# LEDMatrix.net
KiCad netlist of a schematic drawn in EAGLE
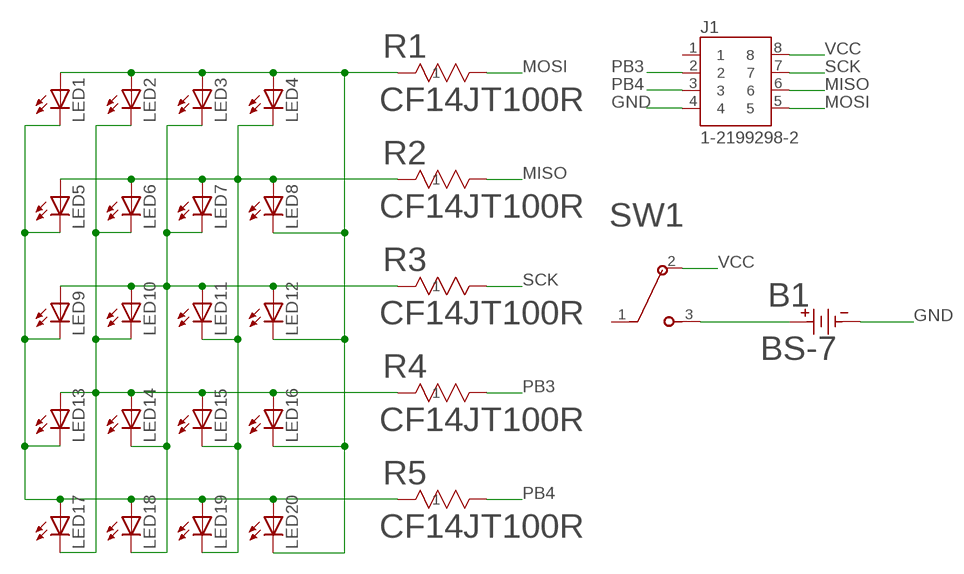
[diagram p0: schematic, sheet 1]

(export (version "E")
  (design (tool "Eeschema 10.0.6"))
  (components
    (comp (ref "B1")
      (value "BS-7")
      (footprint "eagle-import:BS-7_MPD")
      (fields (field (name "COPYRIGHT") "Copyright (C) 2018 Accelerated Designs. All rights reserved"))
      (libsource (lib "eagle-import") (part "BS-7"))
    )
    (comp (ref "J1")
      (value "1-2199298-2")
      (footprint "eagle-import:TE_1-2199298-2")
      (fields (field (name "DIGI-KEY_PART_NUMBER") "A120347-ND") (field (name "MF") "TE Connectivity"))
      (libsource (lib "eagle-import") (part "1-2199298-2"))
    )
    (comp (ref "LED1")
      (value "LED3MM")
      (footprint "eagle-import:LED3MM")
      (libsource (lib "eagle-import") (part "LED3MM"))
    )
    (comp (ref "LED2")
      (value "LED3MM")
      (footprint "eagle-import:LED3MM")
      (libsource (lib "eagle-import") (part "LED3MM"))
    )
    (comp (ref "LED3")
      (value "LED3MM")
      (footprint "eagle-import:LED3MM")
      (libsource (lib "eagle-import") (part "LED3MM"))
    )
    (comp (ref "LED4")
      (value "LED3MM")
      (footprint "eagle-import:LED3MM")
      (libsource (lib "eagle-import") (part "LED3MM"))
    )
    (comp (ref "LED5")
      (value "LED3MM")
      (footprint "eagle-import:LED3MM")
      (libsource (lib "eagle-import") (part "LED3MM"))
    )
    (comp (ref "LED6")
      (value "LED3MM")
      (footprint "eagle-import:LED3MM")
      (libsource (lib "eagle-import") (part "LED3MM"))
    )
    (comp (ref "LED7")
      (value "LED3MM")
      (footprint "eagle-import:LED3MM")
      (libsource (lib "eagle-import") (part "LED3MM"))
    )
    (comp (ref "LED8")
      (value "LED3MM")
      (footprint "eagle-import:LED3MM")
      (libsource (lib "eagle-import") (part "LED3MM"))
    )
    (comp (ref "LED9")
      (value "LED3MM")
      (footprint "eagle-import:LED3MM")
      (libsource (lib "eagle-import") (part "LED3MM"))
    )
    (comp (ref "LED10")
      (value "LED3MM")
      (footprint "eagle-import:LED3MM")
      (libsource (lib "eagle-import") (part "LED3MM"))
    )
    (comp (ref "LED11")
      (value "LED3MM")
      (footprint "eagle-import:LED3MM")
      (libsource (lib "eagle-import") (part "LED3MM"))
    )
    (comp (ref "LED12")
      (value "LED3MM")
      (footprint "eagle-import:LED3MM")
      (libsource (lib "eagle-import") (part "LED3MM"))
    )
    (comp (ref "LED13")
      (value "LED3MM")
      (footprint "eagle-import:LED3MM")
      (libsource (lib "eagle-import") (part "LED3MM"))
    )
    (comp (ref "LED14")
      (value "LED3MM")
      (footprint "eagle-import:LED3MM")
      (libsource (lib "eagle-import") (part "LED3MM"))
    )
    (comp (ref "LED15")
      (value "LED3MM")
      (footprint "eagle-import:LED3MM")
      (libsource (lib "eagle-import") (part "LED3MM"))
    )
    (comp (ref "LED16")
      (value "LED3MM")
      (footprint "eagle-import:LED3MM")
      (libsource (lib "eagle-import") (part "LED3MM"))
    )
    (comp (ref "LED17")
      (value "LED3MM")
      (footprint "eagle-import:LED3MM")
      (libsource (lib "eagle-import") (part "LED3MM"))
    )
    (comp (ref "LED18")
      (value "LED3MM")
      (footprint "eagle-import:LED3MM")
      (libsource (lib "eagle-import") (part "LED3MM"))
    )
    (comp (ref "LED19")
      (value "LED3MM")
      (footprint "eagle-import:LED3MM")
      (libsource (lib "eagle-import") (part "LED3MM"))
    )
    (comp (ref "LED20")
      (value "LED3MM")
      (footprint "eagle-import:LED3MM")
      (libsource (lib "eagle-import") (part "LED3MM"))
    )
    (comp (ref "R1")
      (value "CF14JT100R")
      (footprint "eagle-import:STA_CF14_STP")
      (libsource (lib "eagle-import") (part "CF14JT100R"))
    )
    (comp (ref "R2")
      (value "CF14JT100R")
      (footprint "eagle-import:STA_CF14_STP")
      (libsource (lib "eagle-import") (part "CF14JT100R"))
    )
    (comp (ref "R3")
      (value "CF14JT100R")
      (footprint "eagle-import:STA_CF14_STP")
      (libsource (lib "eagle-import") (part "CF14JT100R"))
    )
    (comp (ref "R4")
      (value "CF14JT100R")
      (footprint "eagle-import:STA_CF14_STP")
      (libsource (lib "eagle-import") (part "CF14JT100R"))
    )
    (comp (ref "R5")
      (value "CF14JT100R")
      (footprint "eagle-import:STA_CF14_STP")
      (libsource (lib "eagle-import") (part "CF14JT100R"))
    )
    (comp (ref "SW1")
      (value "EG1218")
      (footprint "eagle-import:SW_1218_EWI")
      (fields (field (name "COPYRIGHT") "Copyright (C) 2018 Accelerated Designs. All rights reserved"))
      (libsource (lib "eagle-import") (part "EG1218"))
    )
  )
  (nets
    (net (code "1") (name "/GND") (class "Default")
      (node (ref "B1") (pin "1") (pinfunction "1_1") (pintype "passive"))
      (node (ref "J1") (pin "4") (pinfunction "4_4") (pintype "passive"))
    )
    (net (code "2") (name "/MISO") (class "Default")
      (node (ref "J1") (pin "6") (pinfunction "6_6") (pintype "passive"))
      (node (ref "R2") (pin "2") (pinfunction "2_2") (pintype "passive"))
    )
    (net (code "3") (name "/MOSI") (class "Default")
      (node (ref "J1") (pin "5") (pinfunction "5_5") (pintype "passive"))
      (node (ref "R1") (pin "2") (pinfunction "2_2") (pintype "passive"))
    )
    (net (code "4") (name "/PB3") (class "Default")
      (node (ref "J1") (pin "2") (pinfunction "2_2") (pintype "passive"))
      (node (ref "R4") (pin "2") (pinfunction "2_2") (pintype "passive"))
    )
    (net (code "5") (name "/PB4") (class "Default")
      (node (ref "J1") (pin "3") (pinfunction "3_3") (pintype "passive"))
      (node (ref "R5") (pin "2") (pinfunction "2_2") (pintype "passive"))
    )
    (net (code "6") (name "/SCK") (class "Default")
      (node (ref "J1") (pin "7") (pinfunction "7_7") (pintype "passive"))
      (node (ref "R3") (pin "2") (pinfunction "2_2") (pintype "passive"))
    )
    (net (code "7") (name "/VCC") (class "Default")
      (node (ref "J1") (pin "8") (pinfunction "8_8") (pintype "passive"))
      (node (ref "SW1") (pin "2") (pinfunction "2_2") (pintype "passive"))
    )
    (net (code "8") (name "Net-(B1-Pad2)") (class "Default")
      (node (ref "B1") (pin "2") (pinfunction "2_2") (pintype "passive"))
      (node (ref "SW1") (pin "3") (pinfunction "3_3") (pintype "passive"))
    )
    (net (code "9") (name "Net-(LED1-C)") (class "Default")
      (node (ref "LED1") (pin "K") (pinfunction "C_K") (pintype "passive"))
      (node (ref "LED13") (pin "K") (pinfunction "C_K") (pintype "passive"))
      (node (ref "LED17") (pin "A") (pinfunction "A_A") (pintype "passive"))
      (node (ref "LED18") (pin "A") (pinfunction "A_A") (pintype "passive"))
      (node (ref "LED19") (pin "A") (pinfunction "A_A") (pintype "passive"))
      (node (ref "LED20") (pin "A") (pinfunction "A_A") (pintype "passive"))
      (node (ref "LED5") (pin "K") (pinfunction "C_K") (pintype "passive"))
      (node (ref "LED9") (pin "K") (pinfunction "C_K") (pintype "passive"))
      (node (ref "R5") (pin "1") (pinfunction "1_1") (pintype "passive"))
    )
    (net (code "10") (name "Net-(LED10-C)") (class "Default")
      (node (ref "LED10") (pin "K") (pinfunction "C_K") (pintype "passive"))
      (node (ref "LED13") (pin "A") (pinfunction "A_A") (pintype "passive"))
      (node (ref "LED14") (pin "A") (pinfunction "A_A") (pintype "passive"))
      (node (ref "LED15") (pin "A") (pinfunction "A_A") (pintype "passive"))
      (node (ref "LED16") (pin "A") (pinfunction "A_A") (pintype "passive"))
      (node (ref "LED17") (pin "K") (pinfunction "C_K") (pintype "passive"))
      (node (ref "LED2") (pin "K") (pinfunction "C_K") (pintype "passive"))
      (node (ref "LED6") (pin "K") (pinfunction "C_K") (pintype "passive"))
      (node (ref "R4") (pin "1") (pinfunction "1_1") (pintype "passive"))
    )
    (net (code "11") (name "Net-(LED11-C)") (class "Default")
      (node (ref "LED11") (pin "K") (pinfunction "C_K") (pintype "passive"))
      (node (ref "LED15") (pin "K") (pinfunction "C_K") (pintype "passive"))
      (node (ref "LED19") (pin "K") (pinfunction "C_K") (pintype "passive"))
      (node (ref "LED4") (pin "K") (pinfunction "C_K") (pintype "passive"))
      (node (ref "LED5") (pin "A") (pinfunction "A_A") (pintype "passive"))
      (node (ref "LED6") (pin "A") (pinfunction "A_A") (pintype "passive"))
      (node (ref "LED7") (pin "A") (pinfunction "A_A") (pintype "passive"))
      (node (ref "LED8") (pin "A") (pinfunction "A_A") (pintype "passive"))
      (node (ref "R2") (pin "1") (pinfunction "1_1") (pintype "passive"))
    )
    (net (code "12") (name "Net-(LED12-C)") (class "Default")
      (node (ref "LED1") (pin "A") (pinfunction "A_A") (pintype "passive"))
      (node (ref "LED12") (pin "K") (pinfunction "C_K") (pintype "passive"))
      (node (ref "LED16") (pin "K") (pinfunction "C_K") (pintype "passive"))
      (node (ref "LED2") (pin "A") (pinfunction "A_A") (pintype "passive"))
      (node (ref "LED20") (pin "K") (pinfunction "C_K") (pintype "passive"))
      (node (ref "LED3") (pin "A") (pinfunction "A_A") (pintype "passive"))
      (node (ref "LED4") (pin "A") (pinfunction "A_A") (pintype "passive"))
      (node (ref "LED8") (pin "K") (pinfunction "C_K") (pintype "passive"))
      (node (ref "R1") (pin "1") (pinfunction "1_1") (pintype "passive"))
    )
    (net (code "13") (name "Net-(LED14-C)") (class "Default")
      (node (ref "LED10") (pin "A") (pinfunction "A_A") (pintype "passive"))
      (node (ref "LED11") (pin "A") (pinfunction "A_A") (pintype "passive"))
      (node (ref "LED12") (pin "A") (pinfunction "A_A") (pintype "passive"))
      (node (ref "LED14") (pin "K") (pinfunction "C_K") (pintype "passive"))
      (node (ref "LED18") (pin "K") (pinfunction "C_K") (pintype "passive"))
      (node (ref "LED3") (pin "K") (pinfunction "C_K") (pintype "passive"))
      (node (ref "LED7") (pin "K") (pinfunction "C_K") (pintype "passive"))
      (node (ref "LED9") (pin "A") (pinfunction "A_A") (pintype "passive"))
      (node (ref "R3") (pin "1") (pinfunction "1_1") (pintype "passive"))
    )
    (net (code "14") (name "unconnected-(J1-Pad1)") (class "Default")
      (node (ref "J1") (pin "1") (pinfunction "1_1") (pintype "passive"))
    )
    (net (code "15") (name "unconnected-(SW1-Pad1)") (class "Default")
      (node (ref "SW1") (pin "1") (pinfunction "1_1") (pintype "passive"))
    )
  )
)
